# RTC.net
KiCad netlist of a schematic drawn in Altium Designer
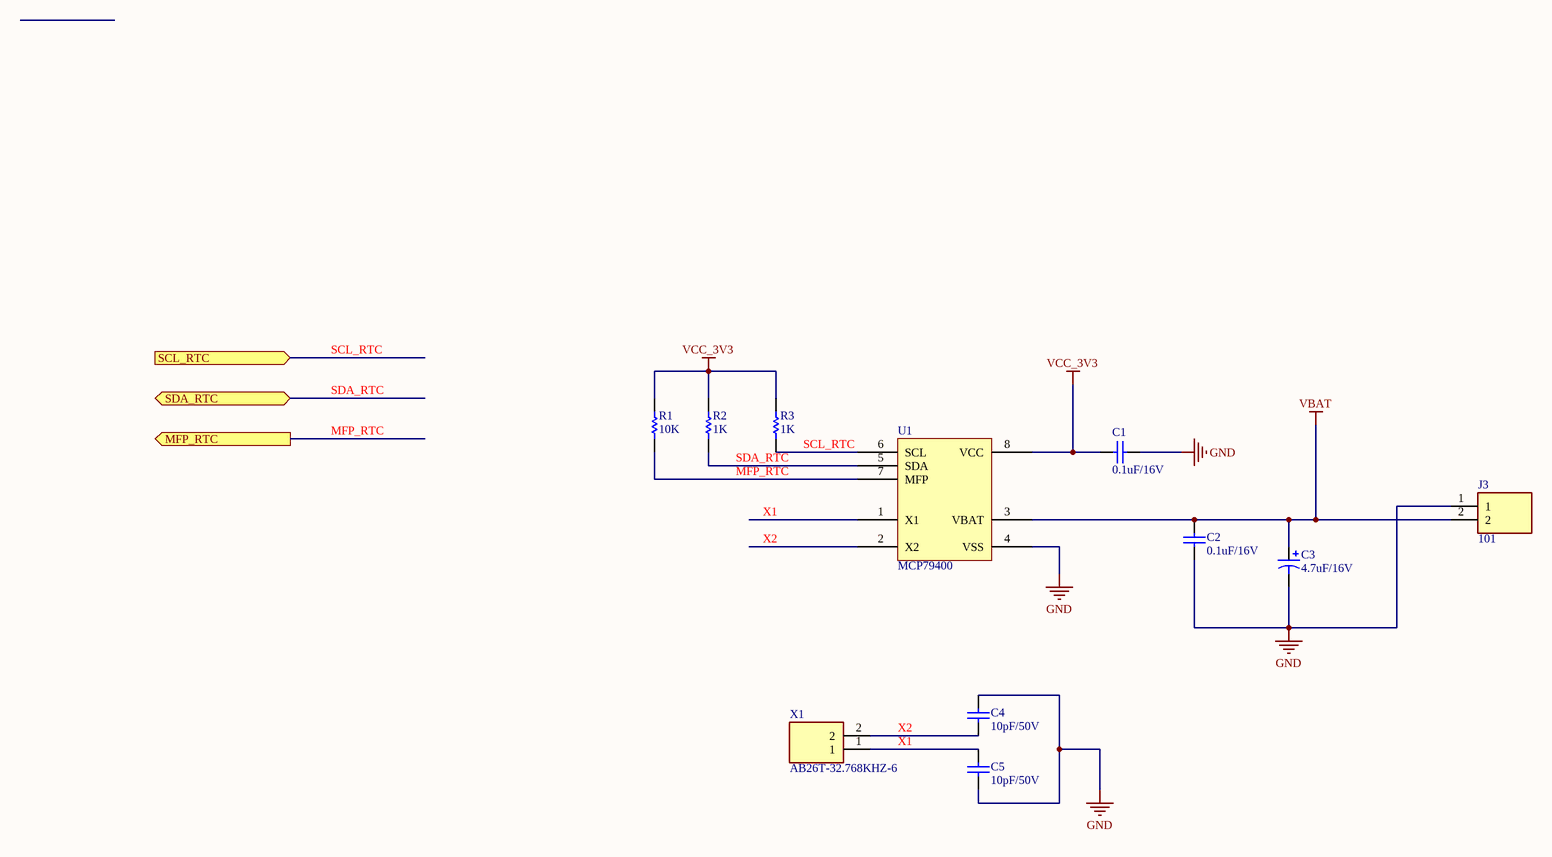
[diagram p0: RTC.SchDoc]

(export (version "E")
  (design (tool "Eeschema 10.0.6"))
  (components
    (comp (ref "C1")
      (value "0.1uF/16V")
      (footprint "0603C")
      (description "Multilayer Ceramic Capacitors MLCC - SMD/SMT 0603 16VDC 0.1uF 10% X7R AEC-Q2000")
      (fields (field (name "MFR") "Taiyo Yuden") (field (name "MFR PART NO") "EMK107B7104KAHT"))
      (libsource (lib "Miscellaneous Devices") (part "Cap"))
    )
    (comp (ref "C2")
      (value "0.1uF/16V")
      (footprint "0603C")
      (description "Multilayer Ceramic Capacitors MLCC - SMD/SMT 0603 16VDC 0.1uF 10% X7R AEC-Q2000")
      (fields
        (field (name "MFR PART NO") "EMK107B7104KAHT")
        (field (name "STOCKIEST PART NO") "963-EMK107B7104KAHT")
      )
      (libsource (lib "Myde10") (part "0805_CAP"))
    )
    (comp (ref "C3")
      (value "4.7uF/16V")
      (footprint "CASE-A")
      (description "Tantalum Capacitors - Solid SMD 16V 4.7uF 1206")
      (fields (field (name "MFR") "KEMET") (field (name "MFR PART NO") "T495A475K016ATA2K0"))
      (libsource (lib "Miscellaneous Devices") (part "Cap Pol1"))
    )
    (comp (ref "C4")
      (value "10pF/50V")
      (footprint "0603C")
      (description "Multilayer Ceramic Capacitors MLCC - SMD/SMT 50V 10pF 0603 C0G 5% AEC-Q200")
      (fields (field (name "MFR") "KEMET") (field (name "MFR PART NO") "C0603C100J5GACAUTO"))
      (libsource (lib "Miscellaneous Devices") (part "Cap"))
    )
    (comp (ref "C5")
      (value "10pF/50V")
      (footprint "0603C")
      (description "Multilayer Ceramic Capacitors MLCC - SMD/SMT 50V 10pF 0603 C0G 5% AEC-Q200")
      (fields (field (name "MFR") "KEMET") (field (name "MFR PART NO") "C0603C100J5GACAUTO"))
      (libsource (lib "Miscellaneous Devices") (part "Cap"))
    )
    (comp (ref "J3")
      (value "101")
      (footprint "101")
      (description "Coin Cell Battery Holders 20mm coin cell HOLDER")
      (fields (field (name "STOCKIEST PART NO") "534-101"))
      (libsource (lib "*") (part "101"))
    )
    (comp (ref "R1")
      (value "10K")
      (footprint "0603R")
      (description "Thick Film Resistors - SMD 0603 10Kohms 1% Anti-Sulfur AEC-Q200")
      (fields (field (name "MFR") "ROHM Semiconductor") (field (name "MFR PART NO") "SFR03EZPF1002"))
      (libsource (lib "Miscellaneous Devices") (part "Res1"))
    )
    (comp (ref "R2")
      (value "1K")
      (footprint "0603R")
      (description "Resistor")
      (fields (field (name "MFR") "Vishay / Dale") (field (name "MFR PART NO") "CRCW06031K00FKEAC"))
      (libsource (lib "Miscellaneous Devices") (part "Res1"))
    )
    (comp (ref "R3")
      (value "1K")
      (footprint "0603R")
      (description "Resistor")
      (fields (field (name "MFR") "Vishay / Dale") (field (name "MFR PART NO") "CRCW06031K00FKEAC"))
      (libsource (lib "Miscellaneous Devices") (part "Res1"))
    )
    (comp (ref "U1")
      (value "MCP79400")
      (footprint "MCP79400-I/SN")
      (description "Real Time Clock I2C GP RTCC 64B SRAM ID")
      (fields (field (name "MFR") "Microchip Technology") (field (name "MFR PART NO") "MCP79400-I/SN"))
      (libsource (lib "Schlib1") (part "MCP79400"))
    )
    (comp (ref "X1")
      (value "AB26T-32.768KHZ-6")
      (footprint "AB26T32768KHZE")
      (description "Crystals 32.768KHz 6pF 32.768KHZ")
      (fields (field (name "MFR") "ABRACON") (field (name "STOCKIEST PART NO") "815-AB26T-32.768K-6"))
      (libsource (lib "*") (part "AB26T-32.768KHZ-6"))
    )
  )
  (nets
    (net (code "1") (name "/MFP_RTC") (class "Default")
      (node (ref "R1") (pin "1") (pinfunction "1_1") (pintype "passive"))
      (node (ref "U1") (pin "7") (pinfunction "MFP_7") (pintype "passive"))
    )
    (net (code "2") (name "/SCL_RTC") (class "Default")
      (node (ref "R3") (pin "1") (pinfunction "1_1") (pintype "passive"))
      (node (ref "U1") (pin "6") (pinfunction "SCL_6") (pintype "passive"))
    )
    (net (code "3") (name "/SDA_RTC") (class "Default")
      (node (ref "R2") (pin "1") (pinfunction "1_1") (pintype "passive"))
      (node (ref "U1") (pin "5") (pinfunction "SDA_5") (pintype "passive"))
    )
    (net (code "4") (name "/X1") (class "Default")
      (node (ref "C5") (pin "1") (pinfunction "1_1") (pintype "passive"))
      (node (ref "U1") (pin "1") (pinfunction "X1_1") (pintype "passive"))
      (node (ref "X1") (pin "1") (pinfunction "1_1") (pintype "passive"))
    )
    (net (code "5") (name "/X2") (class "Default")
      (node (ref "C4") (pin "2") (pinfunction "2_2") (pintype "passive"))
      (node (ref "U1") (pin "2") (pinfunction "X2_2") (pintype "passive"))
      (node (ref "X1") (pin "2") (pinfunction "2_2") (pintype "passive"))
    )
    (net (code "6") (name "GND") (class "Default")
      (node (ref "C1") (pin "2") (pinfunction "2_2") (pintype "passive"))
      (node (ref "C2") (pin "2") (pinfunction "2_2") (pintype "passive"))
      (node (ref "C3") (pin "2") (pinfunction "2_2") (pintype "passive"))
      (node (ref "C4") (pin "1") (pinfunction "1_1") (pintype "passive"))
      (node (ref "C5") (pin "2") (pinfunction "2_2") (pintype "passive"))
      (node (ref "J3") (pin "1") (pinfunction "1_1") (pintype "passive"))
      (node (ref "U1") (pin "4") (pinfunction "VSS_4") (pintype "passive"))
    )
    (net (code "7") (name "VBAT") (class "Default")
      (node (ref "C2") (pin "1") (pinfunction "1_1") (pintype "passive"))
      (node (ref "C3") (pin "1") (pinfunction "1_1") (pintype "passive"))
      (node (ref "J3") (pin "2") (pinfunction "2_2") (pintype "passive"))
      (node (ref "U1") (pin "3") (pinfunction "VBAT_3") (pintype "passive"))
    )
    (net (code "8") (name "VCC_3V3") (class "Default")
      (node (ref "C1") (pin "1") (pinfunction "1_1") (pintype "passive"))
      (node (ref "R1") (pin "2") (pinfunction "2_2") (pintype "passive"))
      (node (ref "R2") (pin "2") (pinfunction "2_2") (pintype "passive"))
      (node (ref "R3") (pin "2") (pinfunction "2_2") (pintype "passive"))
      (node (ref "U1") (pin "8") (pinfunction "VCC_8") (pintype "passive"))
    )
  )
)
